# switch-smd-16mm-mk-1_0.net
KiCad netlist of a schematic drawn in EAGLE
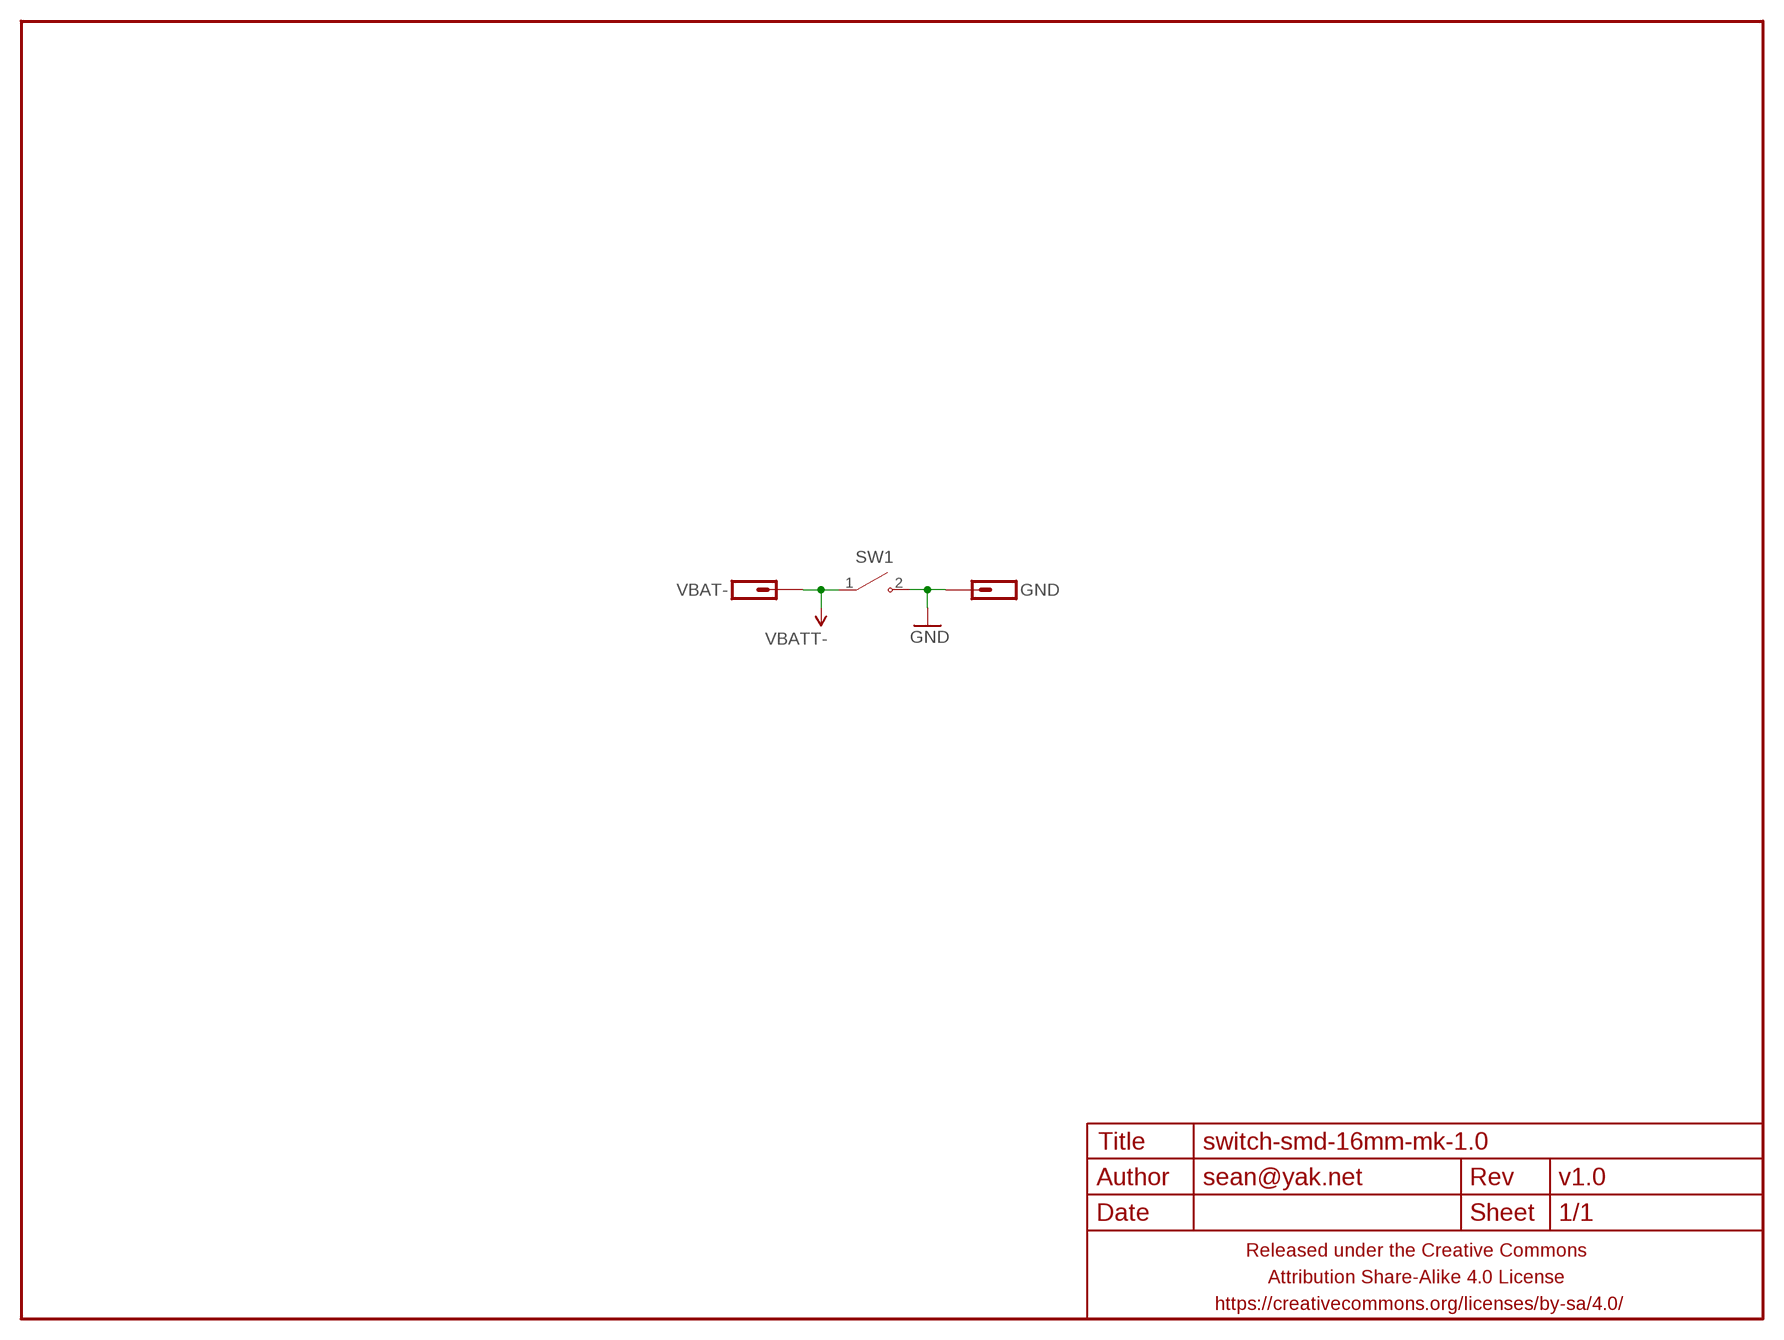
[diagram p0: schematic, sheet 1]

(export (version "E")
  (design (tool "Eeschema 10.0.6"))
  (components
    (comp (ref "FRAME1")
      (value "FRAME-LETTERNO_PACKAGE")
      (footprint "eagle-import:DUMMY")
      (fields (field (name "DESIGNER") "sean@yak.net") (field (name "VERSION") "v1.0"))
      (libsource (lib "eagle-import") (part "FRAME-LETTERNO_PACKAGE"))
    )
    (comp (ref "GND")
      (value "M01NOT-A-VIA-NOPE")
      (footprint "eagle-import:1X01_NOSILK_NOSTOP")
      (libsource (lib "eagle-import") (part "M01NOT-A-VIA-NOPE"))
    )
    (comp (ref "SW1")
      (value "SWITCH-SPSTOMTEN-1288-LESS2")
      (footprint "eagle-import:OMTEN-1288-LESS2")
      (libsource (lib "eagle-import") (part "SWITCH-SPSTOMTEN-1288-LESS2"))
    )
    (comp (ref "VBAT-")
      (value "M01PTH-1.2MM-NS")
      (footprint "eagle-import:1X01-1.2MM-NS")
      (libsource (lib "eagle-import") (part "M01PTH-1.2MM-NS"))
    )
  )
  (nets
    (net (code "1") (name "GND") (class "Default")
      (node (ref "GND") (pin "P$1") (pinfunction "1_P$1") (pintype "passive"))
      (node (ref "SW1") (pin "2") (pinfunction "NO_2") (pintype "bidirectional"))
    )
    (net (code "2") (name "VBATT-") (class "Default")
      (node (ref "SW1") (pin "1") (pinfunction "COM_1") (pintype "bidirectional"))
      (node (ref "VBAT-") (pin "P$1") (pinfunction "1_P$1") (pintype "passive"))
    )
  )
)
